# BreadBoardPS-882.net
KiCad netlist of a schematic drawn in EAGLE
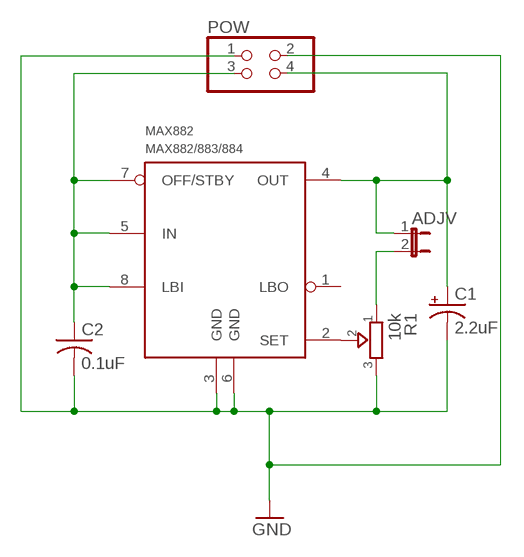
[diagram p0: schematic, sheet 1]

(export (version "E")
  (design (tool "Eeschema 10.0.6"))
  (components
    (comp (ref "ADJV")
      (value "JP1E")
      (footprint "eagle-import:JP1")
      (libsource (lib "eagle-import") (part "JP1E"))
    )
    (comp (ref "C1")
      (value "2.2uF")
      (footprint "eagle-import:E2,5-5")
      (libsource (lib "eagle-import") (part "CPOL-USE2.5-5"))
    )
    (comp (ref "C2")
      (value "0.1uF")
      (footprint "eagle-import:C025-024X044")
      (libsource (lib "eagle-import") (part "C-US025-024X044"))
    )
    (comp (ref "MAX882")
      (value "MAX882/883/884")
      (footprint "eagle-import:DIL08")
      (libsource (lib "eagle-import") (part "MAX882/883/884"))
    )
    (comp (ref "POW")
      (value "PINHD-2X22X02/90NOSILK")
      (footprint "eagle-import:2X02_90")
      (libsource (lib "eagle-import") (part "PINHD-2X22X02/90NOSILK"))
    )
    (comp (ref "R1")
      (value "10k")
      (footprint "eagle-import:TRIMMER_3306F")
      (libsource (lib "eagle-import") (part "TRIMMER-3306F"))
    )
  )
  (nets
    (net (code "1") (name "GND") (class "Default")
      (node (ref "C1") (pin "-") (pinfunction "-_-") (pintype "passive"))
      (node (ref "C2") (pin "2") (pinfunction "2_2") (pintype "passive"))
      (node (ref "MAX882") (pin "3") (pinfunction "GND_3") (pintype "power_in"))
      (node (ref "MAX882") (pin "6") (pinfunction "GND_6") (pintype "power_in"))
      (node (ref "POW") (pin "1") (pinfunction "1_1") (pintype "passive"))
      (node (ref "POW") (pin "2") (pinfunction "2_2") (pintype "passive"))
      (node (ref "R1") (pin "3") (pinfunction "3_3") (pintype "passive"))
    )
    (net (code "2") (name "Net-(ADJV-Pad2)") (class "Default")
      (node (ref "ADJV") (pin "2") (pinfunction "2_2") (pintype "passive"))
      (node (ref "R1") (pin "1") (pinfunction "1_1") (pintype "passive"))
    )
    (net (code "3") (name "Net-(MAX882-IN)") (class "Default")
      (node (ref "C2") (pin "1") (pinfunction "1_1") (pintype "passive"))
      (node (ref "MAX882") (pin "5") (pinfunction "IN_5") (pintype "power_in"))
      (node (ref "MAX882") (pin "7") (pinfunction "OFF/STBY_7") (pintype "passive"))
      (node (ref "MAX882") (pin "8") (pinfunction "LBI_8") (pintype "passive"))
      (node (ref "POW") (pin "3") (pinfunction "3_3") (pintype "passive"))
    )
    (net (code "4") (name "Net-(MAX882-OUT)") (class "Default")
      (node (ref "ADJV") (pin "1") (pinfunction "1_1") (pintype "passive"))
      (node (ref "C1") (pin "+") (pinfunction "+_+") (pintype "passive"))
      (node (ref "MAX882") (pin "4") (pinfunction "OUT_4") (pintype "power_in"))
      (node (ref "POW") (pin "4") (pinfunction "4_4") (pintype "passive"))
    )
    (net (code "5") (name "Net-(MAX882-SET)") (class "Default")
      (node (ref "MAX882") (pin "2") (pinfunction "SET_2") (pintype "passive"))
      (node (ref "R1") (pin "2") (pinfunction "2_2") (pintype "passive"))
    )
    (net (code "6") (name "unconnected-(MAX882-LBO-Pad1)") (class "Default")
      (node (ref "MAX882") (pin "1") (pinfunction "LBO_1") (pintype "open_collector"))
    )
  )
)
